# RTD.net
KiCad netlist of a schematic drawn in Altium Designer
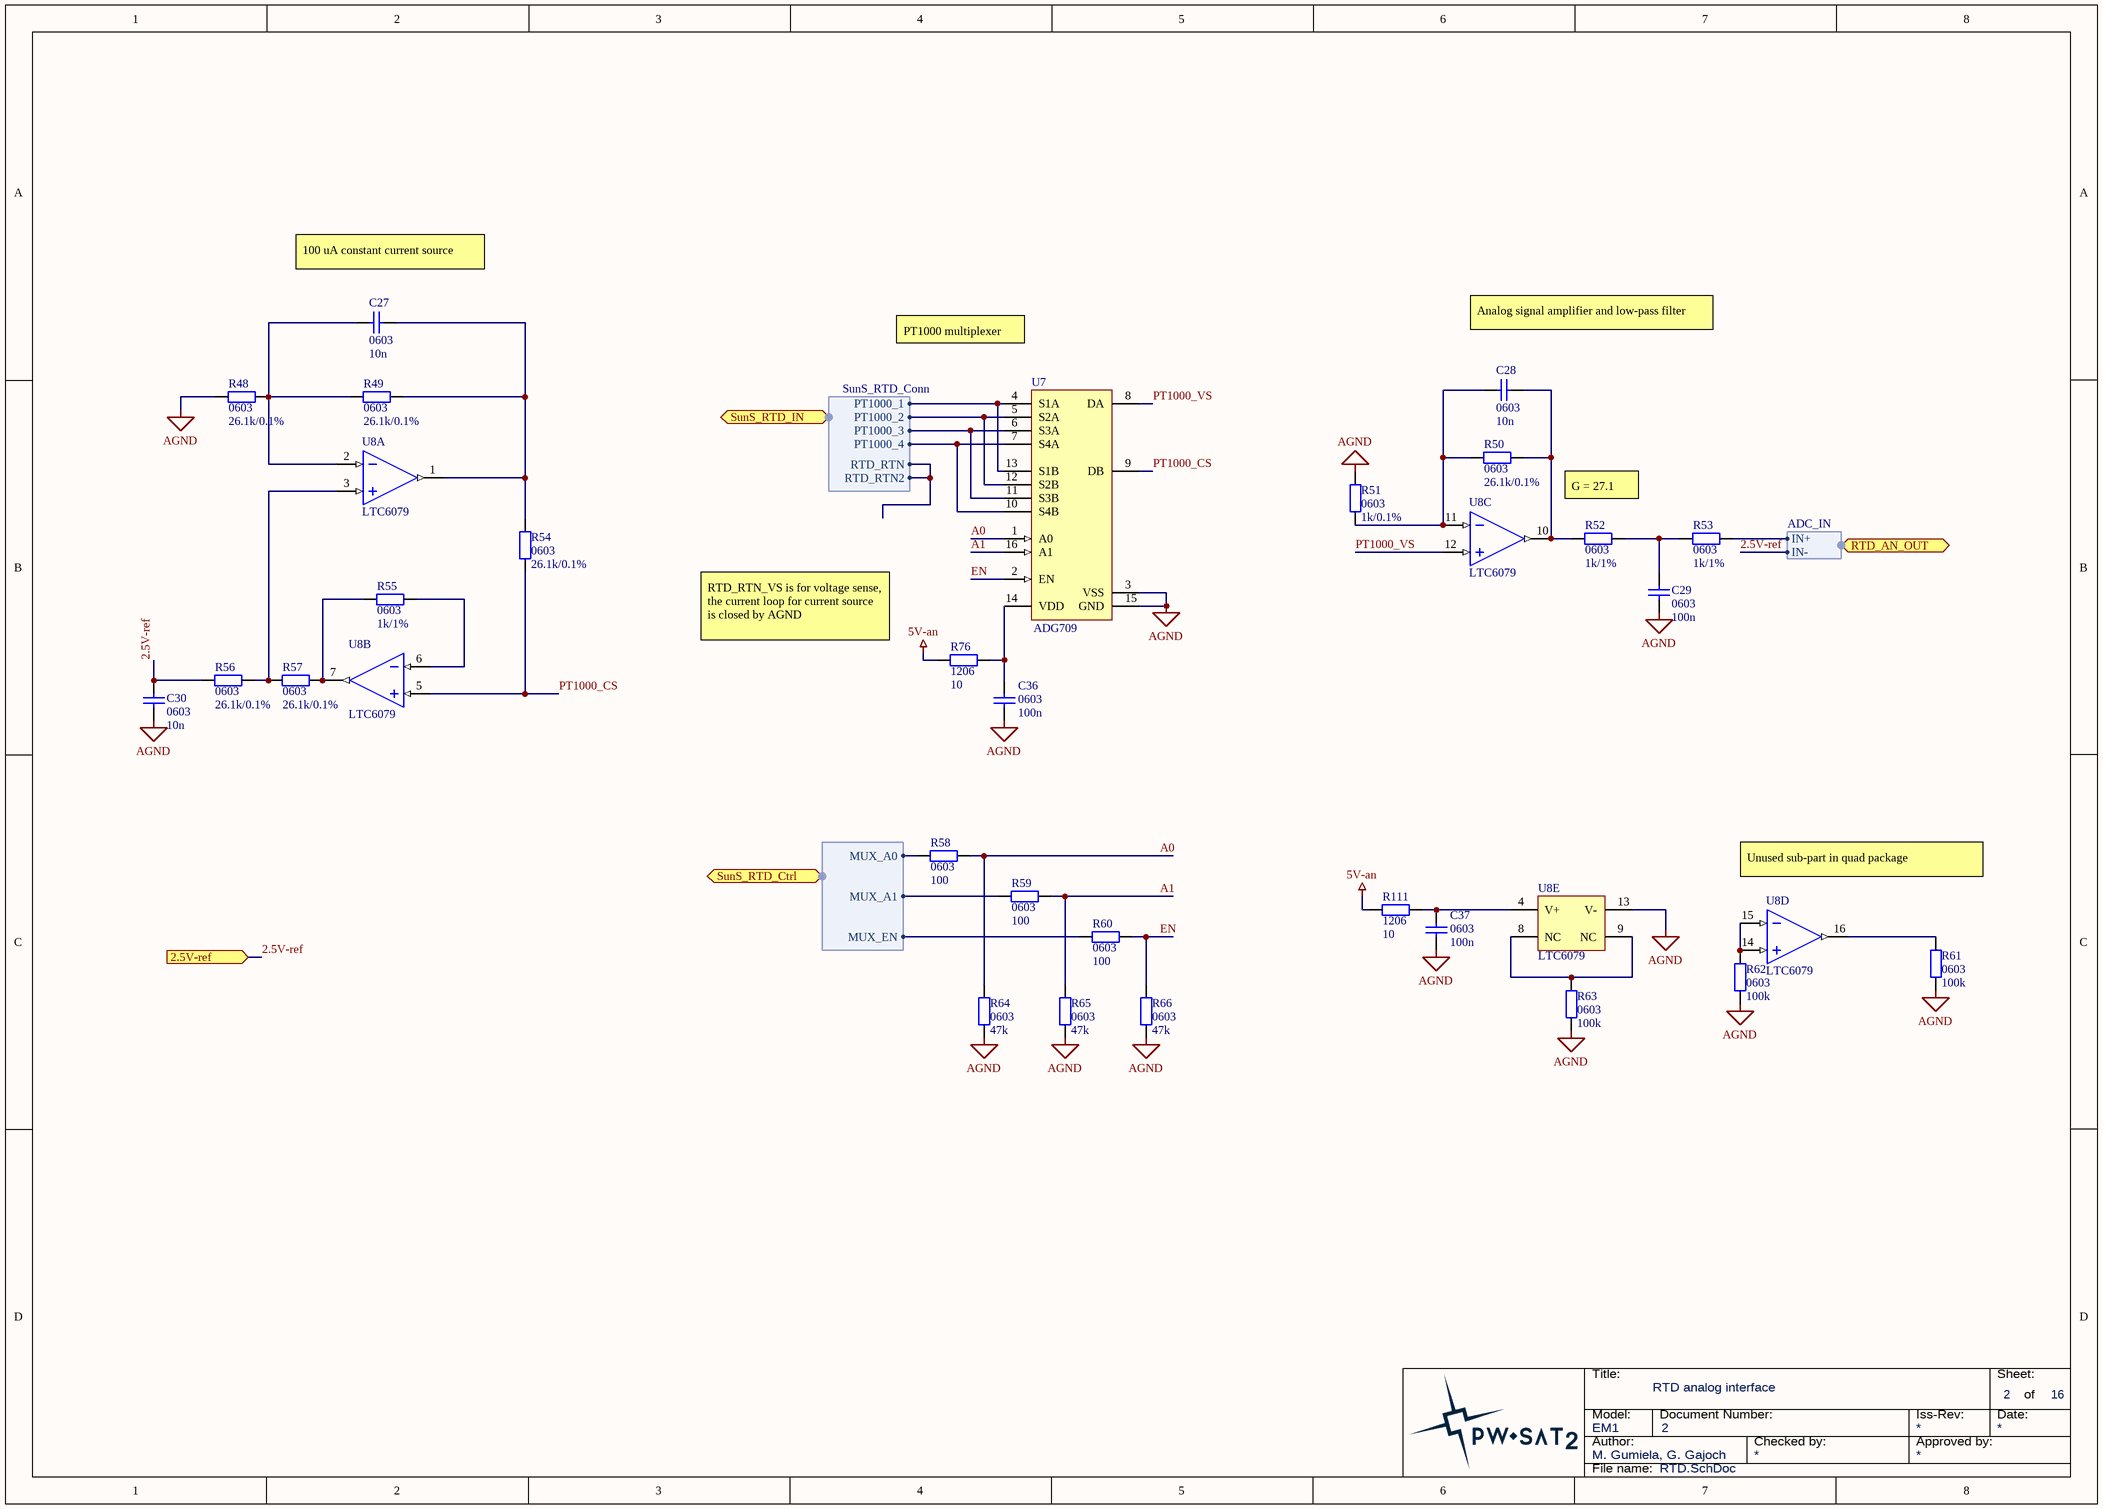
[diagram p0: RTD.SchDoc]

(export (version "E")
  (design (tool "Eeschema 10.0.6"))
  (components
    (comp (ref "C27")
      (value "0603")
      (footprint "SMD_Capacitor_0603")
      (description "Capacitor")
      (fields (field (name "ALTIUM_VALUE") "10n") (field (name "PUBLISHER") "Altium Limited"))
      (libsource (lib "Miscellaneous Devices") (part "Cap"))
    )
    (comp (ref "C28")
      (value "0603")
      (footprint "SMD_Capacitor_0603")
      (description "Capacitor")
      (fields (field (name "ALTIUM_VALUE") "10n") (field (name "PUBLISHER") "Altium Limited"))
      (libsource (lib "Miscellaneous Devices") (part "Cap"))
    )
    (comp (ref "C29")
      (value "0603")
      (footprint "SMD_Capacitor_0603")
      (description "Capacitor")
      (fields (field (name "ALTIUM_VALUE") "100n") (field (name "PUBLISHER") "Altium Limited"))
      (libsource (lib "Miscellaneous Devices") (part "Cap"))
    )
    (comp (ref "C30")
      (value "0603")
      (footprint "SMD_Capacitor_0603")
      (description "Capacitor")
      (fields (field (name "ALTIUM_VALUE") "10n") (field (name "PUBLISHER") "Altium Limited"))
      (libsource (lib "Miscellaneous Devices") (part "Cap"))
    )
    (comp (ref "C36")
      (value "0603")
      (footprint "SMD_Capacitor_0603")
      (description "Capacitor")
      (fields (field (name "ALTIUM_VALUE") "100n") (field (name "PUBLISHER") "Altium Limited"))
      (libsource (lib "Miscellaneous Devices") (part "Cap"))
    )
    (comp (ref "C37")
      (value "0603")
      (footprint "SMD_Capacitor_0603")
      (description "Capacitor")
      (fields (field (name "ALTIUM_VALUE") "100n") (field (name "PUBLISHER") "Altium Limited"))
      (libsource (lib "Miscellaneous Devices") (part "Cap"))
    )
    (comp (ref "R48")
      (value "0603")
      (footprint "SMD_Resistor_0603")
      (description "Resistor")
      (fields (field (name "ALTIUM_VALUE") "26.1k/0.1%") (field (name "PUBLISHER") "Altium Limited"))
      (libsource (lib "Miscellaneous Devices") (part "Res2"))
    )
    (comp (ref "R49")
      (value "0603")
      (footprint "SMD_Resistor_0603")
      (description "Resistor")
      (fields (field (name "ALTIUM_VALUE") "26.1k/0.1%") (field (name "PUBLISHER") "Altium Limited"))
      (libsource (lib "Miscellaneous Devices") (part "Res2"))
    )
    (comp (ref "R50")
      (value "0603")
      (footprint "SMD_Resistor_0603")
      (description "Resistor")
      (fields (field (name "ALTIUM_VALUE") "26.1k/0.1%") (field (name "PUBLISHER") "Altium Limited"))
      (libsource (lib "") (part "Res2_3"))
    )
    (comp (ref "R51")
      (value "0603")
      (footprint "SMD_Resistor_0603")
      (description "Resistor")
      (fields (field (name "ALTIUM_VALUE") "1k/0.1%") (field (name "PUBLISHER") "Altium Limited"))
      (libsource (lib "") (part "Res2_1"))
    )
    (comp (ref "R52")
      (value "0603")
      (footprint "SMD_Resistor_0603")
      (description "Resistor")
      (fields (field (name "ALTIUM_VALUE") "1k/1%") (field (name "PUBLISHER") "Altium Limited"))
      (libsource (lib "Miscellaneous Devices") (part "Res2"))
    )
    (comp (ref "R53")
      (value "0603")
      (footprint "SMD_Resistor_0603")
      (description "Resistor")
      (fields (field (name "ALTIUM_VALUE") "1k/1%") (field (name "PUBLISHER") "Altium Limited"))
      (libsource (lib "Miscellaneous Devices") (part "Res2"))
    )
    (comp (ref "R54")
      (value "0603")
      (footprint "SMD_Resistor_0603")
      (description "Resistor")
      (fields (field (name "ALTIUM_VALUE") "26.1k/0.1%") (field (name "PUBLISHER") "Altium Limited"))
      (libsource (lib "") (part "Res2_2"))
    )
    (comp (ref "R55")
      (value "0603")
      (footprint "SMD_Resistor_0603")
      (description "Resistor")
      (fields (field (name "ALTIUM_VALUE") "1k/1%") (field (name "PUBLISHER") "Altium Limited"))
      (libsource (lib "Miscellaneous Devices") (part "Res2"))
    )
    (comp (ref "R56")
      (value "0603")
      (footprint "SMD_Resistor_0603")
      (description "Resistor")
      (fields (field (name "ALTIUM_VALUE") "26.1k/0.1%") (field (name "PUBLISHER") "Altium Limited"))
      (libsource (lib "Miscellaneous Devices") (part "Res2"))
    )
    (comp (ref "R57")
      (value "0603")
      (footprint "SMD_Resistor_0603")
      (description "Resistor")
      (fields (field (name "ALTIUM_VALUE") "26.1k/0.1%") (field (name "PUBLISHER") "Altium Limited"))
      (libsource (lib "Miscellaneous Devices") (part "Res2"))
    )
    (comp (ref "R58")
      (value "0603")
      (footprint "SMD_Resistor_0603")
      (description "Resistor")
      (fields (field (name "ALTIUM_VALUE") "100") (field (name "PUBLISHER") "Altium Limited"))
      (libsource (lib "") (part "Res2_1"))
    )
    (comp (ref "R59")
      (value "0603")
      (footprint "SMD_Resistor_0603")
      (description "Resistor")
      (fields (field (name "ALTIUM_VALUE") "100") (field (name "PUBLISHER") "Altium Limited"))
      (libsource (lib "") (part "Res2_1"))
    )
    (comp (ref "R60")
      (value "0603")
      (footprint "SMD_Resistor_0603")
      (description "Resistor")
      (fields (field (name "ALTIUM_VALUE") "100") (field (name "PUBLISHER") "Altium Limited"))
      (libsource (lib "") (part "Res2_1"))
    )
    (comp (ref "R61")
      (value "0603")
      (footprint "SMD_Resistor_0603")
      (description "Resistor")
      (fields (field (name "ALTIUM_VALUE") "100k") (field (name "PUBLISHER") "Altium Limited"))
      (libsource (lib "Miscellaneous Devices") (part "Res2"))
    )
    (comp (ref "R62")
      (value "0603")
      (footprint "SMD_Resistor_0603")
      (description "Resistor")
      (fields (field (name "ALTIUM_VALUE") "100k") (field (name "PUBLISHER") "Altium Limited"))
      (libsource (lib "Miscellaneous Devices") (part "Res2"))
    )
    (comp (ref "R63")
      (value "0603")
      (footprint "SMD_Resistor_0603")
      (description "Resistor")
      (fields (field (name "ALTIUM_VALUE") "100k") (field (name "PUBLISHER") "Altium Limited"))
      (libsource (lib "Miscellaneous Devices") (part "Res2"))
    )
    (comp (ref "R64")
      (value "0603")
      (footprint "SMD_Resistor_0603")
      (description "Resistor")
      (fields (field (name "ALTIUM_VALUE") "47k") (field (name "PUBLISHER") "Altium Limited"))
      (libsource (lib "Miscellaneous Devices") (part "Res2"))
    )
    (comp (ref "R65")
      (value "0603")
      (footprint "SMD_Resistor_0603")
      (description "Resistor")
      (fields (field (name "ALTIUM_VALUE") "47k") (field (name "PUBLISHER") "Altium Limited"))
      (libsource (lib "Miscellaneous Devices") (part "Res2"))
    )
    (comp (ref "R66")
      (value "0603")
      (footprint "SMD_Resistor_0603")
      (description "Resistor")
      (fields (field (name "ALTIUM_VALUE") "47k") (field (name "PUBLISHER") "Altium Limited"))
      (libsource (lib "Miscellaneous Devices") (part "Res2"))
    )
    (comp (ref "R76")
      (value "1206")
      (footprint "SMD_Resistor_1206")
      (description "Resistor")
      (fields (field (name "ALTIUM_VALUE") "10") (field (name "PUBLISHER") "Altium Limited"))
      (libsource (lib "") (part "Res2_1"))
    )
    (comp (ref "R111")
      (value "1206")
      (footprint "SMD_Resistor_1206")
      (description "Resistor")
      (fields (field (name "ALTIUM_VALUE") "10") (field (name "PUBLISHER") "Altium Limited"))
      (libsource (lib "") (part "Res2_1"))
    )
    (comp (ref "U7")
      (value "ADG709")
      (footprint "TSSOP16")
      (description "CMOS Analog 4-Channel Multiplexer")
      (fields (field (name "MANUFACTURER") "Analog Devices") (field (name "MANUFACTURERPARTNUMBER") "ADG709"))
      (libsource (lib "microcircuits_miscellaneous") (part "ADG709"))
    )
    (comp (ref "U8")
      (value "LTC6079")
      (footprint "SSOP-16")
      (description "Rail-to-rail, quad operational amplifier. Library compatible with LTC608X LTC607X op-amps")
      (fields (field (name "MANUFACTURER") "Linear Technology"))
      (libsource (lib "") (part "LTC6079_1"))
    )
  )
  (nets
    (net (code "4") (name "/2.5V-ref") (class "Default")
      (node (ref "C30") (pin "1") (pinfunction "1_1") (pintype "passive"))
      (node (ref "R56") (pin "2") (pinfunction "2_2") (pintype "passive"))
    )
    (net (code "5") (name "/A0") (class "Default")
      (node (ref "R58") (pin "1") (pinfunction "1_1") (pintype "passive"))
      (node (ref "R64") (pin "1") (pinfunction "1_1") (pintype "passive"))
      (node (ref "U7") (pin "1") (pinfunction "A0_1") (pintype "input"))
    )
    (net (code "6") (name "/A1") (class "Default")
      (node (ref "R59") (pin "1") (pinfunction "1_1") (pintype "passive"))
      (node (ref "R65") (pin "1") (pinfunction "1_1") (pintype "passive"))
      (node (ref "U7") (pin "16") (pinfunction "A1_16") (pintype "input"))
    )
    (net (code "7") (name "/EN") (class "Default")
      (node (ref "R60") (pin "1") (pinfunction "1_1") (pintype "passive"))
      (node (ref "R66") (pin "1") (pinfunction "1_1") (pintype "passive"))
      (node (ref "U7") (pin "2") (pinfunction "EN_2") (pintype "input"))
    )
    (net (code "8") (name "/IN+") (class "Default")
      (node (ref "R53") (pin "1") (pinfunction "1_1") (pintype "passive"))
    )
    (net (code "9") (name "/MUX_A0") (class "Default")
      (node (ref "R58") (pin "2") (pinfunction "2_2") (pintype "passive"))
    )
    (net (code "10") (name "/MUX_A1") (class "Default")
      (node (ref "R59") (pin "2") (pinfunction "2_2") (pintype "passive"))
    )
    (net (code "11") (name "/MUX_EN") (class "Default")
      (node (ref "R60") (pin "2") (pinfunction "2_2") (pintype "passive"))
    )
    (net (code "12") (name "/PT1000_1") (class "Default")
      (node (ref "U7") (pin "13") (pinfunction "S1B_13") (pintype "passive"))
      (node (ref "U7") (pin "4") (pinfunction "S1A_4") (pintype "passive"))
    )
    (net (code "13") (name "/PT1000_2") (class "Default")
      (node (ref "U7") (pin "12") (pinfunction "S2B_12") (pintype "passive"))
      (node (ref "U7") (pin "5") (pinfunction "S2A_5") (pintype "passive"))
    )
    (net (code "14") (name "/PT1000_3") (class "Default")
      (node (ref "U7") (pin "11") (pinfunction "S3B_11") (pintype "passive"))
      (node (ref "U7") (pin "6") (pinfunction "S3A_6") (pintype "passive"))
    )
    (net (code "15") (name "/PT1000_4") (class "Default")
      (node (ref "U7") (pin "10") (pinfunction "S4B_10") (pintype "passive"))
      (node (ref "U7") (pin "7") (pinfunction "S4A_7") (pintype "passive"))
    )
    (net (code "16") (name "/PT1000_CS") (class "Default")
      (node (ref "R54") (pin "1") (pinfunction "1_1") (pintype "passive"))
      (node (ref "U7") (pin "9") (pinfunction "DB_9") (pintype "passive"))
      (node (ref "U8") (pin "5") (pinfunction "IN+_B_5") (pintype "input"))
    )
    (net (code "17") (name "/PT1000_VS") (class "Default")
      (node (ref "U7") (pin "8") (pinfunction "DA_8") (pintype "passive"))
      (node (ref "U8") (pin "12") (pinfunction "IN+_C_12") (pintype "input"))
    )
    (net (code "22") (name "5V-an") (class "Default")
      (node (ref "R111") (pin "2") (pinfunction "2_2") (pintype "passive"))
      (node (ref "R76") (pin "2") (pinfunction "2_2") (pintype "passive"))
    )
    (net (code "23") (name "AGND") (class "Default")
      (node (ref "C29") (pin "1") (pinfunction "1_1") (pintype "passive"))
      (node (ref "C30") (pin "2") (pinfunction "2_2") (pintype "passive"))
      (node (ref "C36") (pin "1") (pinfunction "1_1") (pintype "passive"))
      (node (ref "C37") (pin "1") (pinfunction "1_1") (pintype "passive"))
      (node (ref "R48") (pin "2") (pinfunction "2_2") (pintype "passive"))
      (node (ref "R51") (pin "1") (pinfunction "1_1") (pintype "passive"))
      (node (ref "R61") (pin "2") (pinfunction "2_2") (pintype "passive"))
      (node (ref "R62") (pin "2") (pinfunction "2_2") (pintype "passive"))
      (node (ref "R63") (pin "2") (pinfunction "2_2") (pintype "passive"))
      (node (ref "R64") (pin "2") (pinfunction "2_2") (pintype "passive"))
      (node (ref "R65") (pin "2") (pinfunction "2_2") (pintype "passive"))
      (node (ref "R66") (pin "2") (pinfunction "2_2") (pintype "passive"))
      (node (ref "U7") (pin "15") (pinfunction "GND_15") (pintype "power_in"))
      (node (ref "U7") (pin "3") (pinfunction "VSS_3") (pintype "power_in"))
      (node (ref "U8") (pin "13") (pinfunction "V-_13") (pintype "power_in"))
    )
    (net (code "24") (name "Net-(C29-Pad2)") (class "Default")
      (node (ref "C29") (pin "2") (pinfunction "2_2") (pintype "passive"))
      (node (ref "R52") (pin "1") (pinfunction "1_1") (pintype "passive"))
      (node (ref "R53") (pin "2") (pinfunction "2_2") (pintype "passive"))
    )
    (net (code "25") (name "Net-(R63-Pad1)") (class "Default")
      (node (ref "R63") (pin "1") (pinfunction "1_1") (pintype "passive"))
      (node (ref "U8") (pin "8") (pinfunction "NC_8") (pintype "passive"))
      (node (ref "U8") (pin "9") (pinfunction "NC_9") (pintype "passive"))
    )
    (net (code "26") (name "Net-(U7-VDD)") (class "Default")
      (node (ref "C36") (pin "2") (pinfunction "2_2") (pintype "passive"))
      (node (ref "R76") (pin "1") (pinfunction "1_1") (pintype "passive"))
      (node (ref "U7") (pin "14") (pinfunction "VDD_14") (pintype "power_in"))
    )
    (net (code "27") (name "Net-(U8A-IN+_A)") (class "Default")
      (node (ref "R56") (pin "1") (pinfunction "1_1") (pintype "passive"))
      (node (ref "R57") (pin "2") (pinfunction "2_2") (pintype "passive"))
      (node (ref "U8") (pin "3") (pinfunction "IN+_A_3") (pintype "input"))
    )
    (net (code "28") (name "Net-(U8A-IN-_A)") (class "Default")
      (node (ref "C27") (pin "1") (pinfunction "1_1") (pintype "passive"))
      (node (ref "R48") (pin "1") (pinfunction "1_1") (pintype "passive"))
      (node (ref "R49") (pin "2") (pinfunction "2_2") (pintype "passive"))
      (node (ref "U8") (pin "2") (pinfunction "IN-_A_2") (pintype "input"))
    )
    (net (code "29") (name "Net-(U8A-OUT_A)") (class "Default")
      (node (ref "C27") (pin "2") (pinfunction "2_2") (pintype "passive"))
      (node (ref "R49") (pin "1") (pinfunction "1_1") (pintype "passive"))
      (node (ref "R54") (pin "2") (pinfunction "2_2") (pintype "passive"))
      (node (ref "U8") (pin "1") (pinfunction "OUT_A_1") (pintype "output"))
    )
    (net (code "30") (name "Net-(U8B-IN-_B)") (class "Default")
      (node (ref "R55") (pin "1") (pinfunction "1_1") (pintype "passive"))
      (node (ref "U8") (pin "6") (pinfunction "IN-_B_6") (pintype "input"))
    )
    (net (code "31") (name "Net-(U8B-OUT_B)") (class "Default")
      (node (ref "R55") (pin "2") (pinfunction "2_2") (pintype "passive"))
      (node (ref "R57") (pin "1") (pinfunction "1_1") (pintype "passive"))
      (node (ref "U8") (pin "7") (pinfunction "OUT_B_7") (pintype "output"))
    )
    (net (code "32") (name "Net-(U8C-IN-_C)") (class "Default")
      (node (ref "C28") (pin "1") (pinfunction "1_1") (pintype "passive"))
      (node (ref "R50") (pin "1") (pinfunction "1_1") (pintype "passive"))
      (node (ref "R51") (pin "2") (pinfunction "2_2") (pintype "passive"))
      (node (ref "U8") (pin "11") (pinfunction "IN-_C_11") (pintype "input"))
    )
    (net (code "33") (name "Net-(U8C-OUT_C)") (class "Default")
      (node (ref "C28") (pin "2") (pinfunction "2_2") (pintype "passive"))
      (node (ref "R50") (pin "2") (pinfunction "2_2") (pintype "passive"))
      (node (ref "R52") (pin "2") (pinfunction "2_2") (pintype "passive"))
      (node (ref "U8") (pin "10") (pinfunction "OUT_C_10") (pintype "output"))
    )
    (net (code "34") (name "Net-(U8D-IN+_D)") (class "Default")
      (node (ref "R62") (pin "1") (pinfunction "1_1") (pintype "passive"))
      (node (ref "U8") (pin "14") (pinfunction "IN+_D_14") (pintype "input"))
      (node (ref "U8") (pin "15") (pinfunction "IN-_D_15") (pintype "input"))
    )
    (net (code "35") (name "Net-(U8D-OUT_D)") (class "Default")
      (node (ref "R61") (pin "1") (pinfunction "1_1") (pintype "passive"))
      (node (ref "U8") (pin "16") (pinfunction "OUT_D_16") (pintype "output"))
    )
    (net (code "36") (name "Net-(U8E-V+)") (class "Default")
      (node (ref "C37") (pin "2") (pinfunction "2_2") (pintype "passive"))
      (node (ref "R111") (pin "1") (pinfunction "1_1") (pintype "passive"))
      (node (ref "U8") (pin "4") (pinfunction "V+_4") (pintype "power_in"))
    )
  )
)
